# URC_ezFET_Lite.net
KiCad netlist of a schematic drawn in Altium Designer
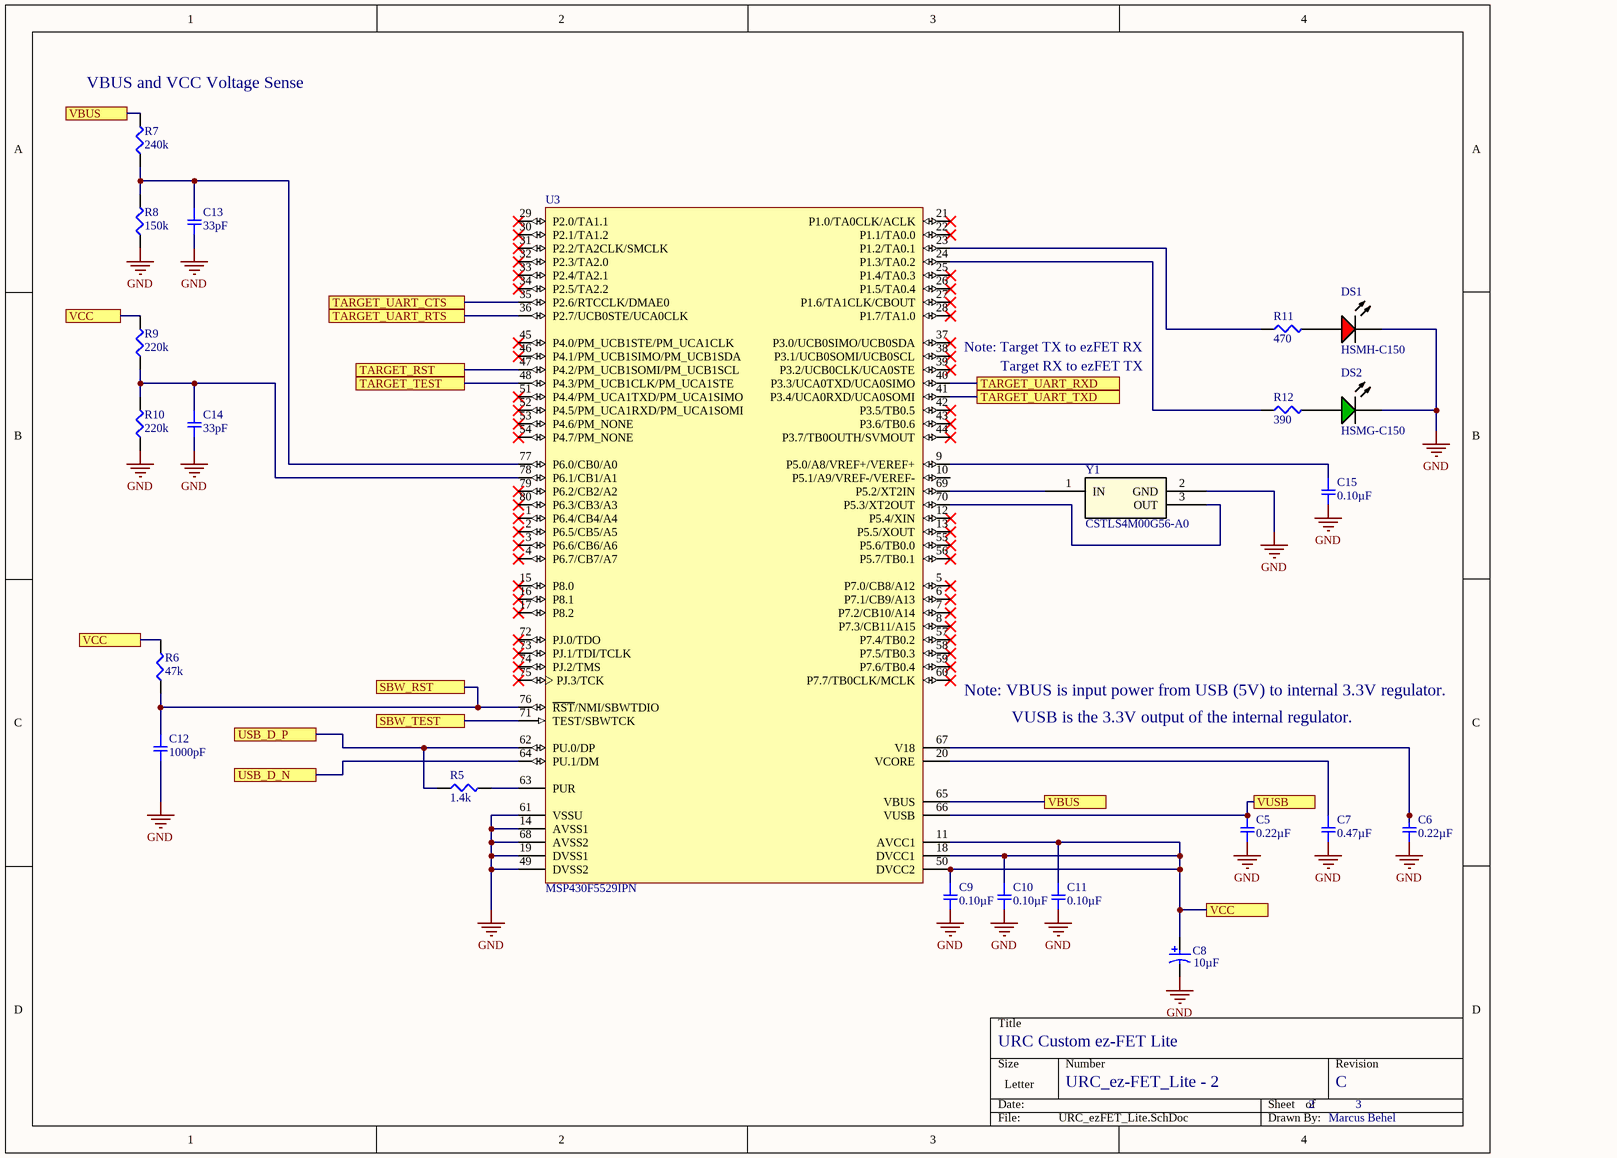
[diagram p0: URC_ezFET_Lite.SchDoc]

(export (version "E")
  (design (tool "Eeschema 10.0.6"))
  (components
    (comp (ref "C5")
      (value "0.22µF")
      (footprint "SMD-1206C")
      (description "CAP CER 0.22UF 50V X7R 1206")
      (fields
        (field (name "DIGI-KEY PART NUMBER") "490-8059-1-ND")
        (field (name "PART NUMBER") "GCM31MR71H224KA37L")
      )
      (libsource (lib "capacitor_murata_1206$") (part "GCM31MR71H224KA37L"))
    )
    (comp (ref "C6")
      (value "0.22µF")
      (footprint "SMD-1206C")
      (description "CAP CER 0.22UF 50V X7R 1206")
      (fields
        (field (name "DIGI-KEY PART NUMBER") "490-8059-1-ND")
        (field (name "PART NUMBER") "GCM31MR71H224KA37L")
      )
      (libsource (lib "capacitor_murata_1206$") (part "GCM31MR71H224KA37L"))
    )
    (comp (ref "C7")
      (value "0.47µF")
      (footprint "SMD-1206C")
      (description "CAP CER 0.47UF 50V X7R 1206")
      (fields
        (field (name "DIGI-KEY PART NUMBER") "490-8061-1-ND")
        (field (name "PART NUMBER") "GCM31MR71H474KA37L")
      )
      (libsource (lib "capacitor_murata_1206$") (part "GCM31MR71H474KA37L"))
    )
    (comp (ref "C8")
      (value "T491A106K010AT")
      (footprint "KEMT-A-3216-18-2_M")
      (description "Capacitor, Tantalum, 10 uF, +/- 10%, 10 V, -55 to 125 degC, 2-Pin SMD (1206), RoHS, Tape and Reel")
      (fields
        (field (name "TOLERANCE") "±10%")
        (field (name "MANUFACTURER") "Kemet")
        (field (name "CAPACITANCE") "10µF")
      )
      (libsource (lib "Altium Content Vault") (part "CAP-P-2"))
    )
    (comp (ref "C9")
      (value "0.10µF")
      (footprint "SMD-1206C")
      (description "CAP CER 0.1UF 50V X7R 1206")
      (fields
        (field (name "DIGI-KEY PART NUMBER") "490-11166-1-ND")
        (field (name "PART NUMBER") "GCM319R71H104KA37D")
      )
      (libsource (lib "capacitor_murata_1206$") (part "GCM319R71H104KA37D"))
    )
    (comp (ref "C10")
      (value "0.10µF")
      (footprint "SMD-1206C")
      (description "CAP CER 0.1UF 50V X7R 1206")
      (fields
        (field (name "DIGI-KEY PART NUMBER") "490-11166-1-ND")
        (field (name "PART NUMBER") "GCM319R71H104KA37D")
      )
      (libsource (lib "capacitor_murata_1206$") (part "GCM319R71H104KA37D"))
    )
    (comp (ref "C11")
      (value "0.10µF")
      (footprint "SMD-1206C")
      (description "CAP CER 0.1UF 50V X7R 1206")
      (fields
        (field (name "DIGI-KEY PART NUMBER") "490-11166-1-ND")
        (field (name "PART NUMBER") "GCM319R71H104KA37D")
      )
      (libsource (lib "capacitor_murata_1206$") (part "GCM319R71H104KA37D"))
    )
    (comp (ref "C12")
      (value "1000pF")
      (footprint "SMD-1206C")
      (description "CAP CER 1000PF 50V X7R 1206")
      (fields
        (field (name "DIGI-KEY PART NUMBER") "490-11610-1-ND")
        (field (name "PART NUMBER") "GRM319R71H102KA01D")
      )
      (libsource (lib "capacitor_murata_1206$") (part "GRM319R71H102KA01D"))
    )
    (comp (ref "C13")
      (value "33pF")
      (footprint "SMD-1206C")
      (description "CAP CER 33PF 630V U2J 1206")
      (fields
        (field (name "DIGI-KEY PART NUMBER") "490-5040-1-ND")
        (field (name "PART NUMBER") "GCM31A7U2J330JX01D")
      )
      (libsource (lib "capacitor_murata_1206$") (part "GCM31A7U2J330JX01D"))
    )
    (comp (ref "C14")
      (value "33pF")
      (footprint "SMD-1206C")
      (description "CAP CER 33PF 630V U2J 1206")
      (fields
        (field (name "DIGI-KEY PART NUMBER") "490-5040-1-ND")
        (field (name "PART NUMBER") "GCM31A7U2J330JX01D")
      )
      (libsource (lib "capacitor_murata_1206$") (part "GCM31A7U2J330JX01D"))
    )
    (comp (ref "C15")
      (value "0.10µF")
      (footprint "SMD-1206C")
      (description "CAP CER 0.1UF 250V X7R 1206")
      (fields
        (field (name "DIGI-KEY PART NUMBER") "490-12647-1-ND")
        (field (name "PART NUMBER") "GCJ31CR72E104KXJ3L")
      )
      (libsource (lib "capacitor_murata_1206$") (part "GCJ31CR72E104KXJ3L"))
    )
    (comp (ref "DS1")
      (value "HSMH-C150")
      (footprint "AVAG-HSMX-C150_V")
      (description "LED Uni-Color Red, 65 mW, 25 mA, -40 to 85 degC, 2-Pin SMD, RoHS, Tape and Reel")
      (fields (field (name "MANUFACTURER") "Avago"))
      (libsource (lib "Altium Content Vault") (part "LED-RED-AK-2"))
    )
    (comp (ref "DS2")
      (value "HSMG-C150")
      (footprint "AVAG-HSMX-C150_V")
      (description "Chip LED, Green, 65 mW, 25 mA, -40 to 85 degC, 2-Pin SMD, RoHS, Tape and Reel")
      (fields (field (name "MANUFACTURER") "Avago"))
      (libsource (lib "Altium Content Vault") (part "LED_GREEN_A1K2-2"))
    )
    (comp (ref "R5")
      (value "1.4k")
      (footprint "SMD-0805-RES")
      (description "RES SMD 1.4K OHM 1% 1/8W 0805")
      (fields
        (field (name "PART NUMBER") "ERJ-6ENF1401V")
        (field (name "DIGI-KEY PART NUMBER") "P1.40KCCT-ND")
      )
      (libsource (lib "Panasonic_ERJ_0805") (part "ERJ-6ENF1401V"))
    )
    (comp (ref "R6")
      (value "47k")
      (footprint "SMD-1206-RES")
      (description "RES SMD 47K OHM 5% 2/3W 1206")
      (fields (field (name "PART NUMBER") "ERJ-P08J473V") (field (name "DIGI-KEY PART NUMBER") "P47KALCT-ND"))
      (libsource (lib "Panasonic_ERJ_1206") (part "ERJ-P08J473V"))
    )
    (comp (ref "R7")
      (value "240k")
      (footprint "SMD-1206-RES")
      (description "RES SMD 240K OHM 5% 2/3W 1206")
      (fields
        (field (name "PART NUMBER") "ERJ-P08J244V")
        (field (name "DIGI-KEY PART NUMBER") "P240KALCT-ND")
      )
      (libsource (lib "Panasonic_ERJ_1206") (part "ERJ-P08J244V"))
    )
    (comp (ref "R8")
      (value "150k")
      (footprint "SMD-1206-RES")
      (description "RES SMD 150K OHM 5% 2/3W 1206")
      (fields
        (field (name "PART NUMBER") "ERJ-P08J154V")
        (field (name "DIGI-KEY PART NUMBER") "P150KALCT-ND")
      )
      (libsource (lib "Panasonic_ERJ_1206") (part "ERJ-P08J154V"))
    )
    (comp (ref "R9")
      (value "220k")
      (footprint "SMD-1206-RES")
      (description "RES SMD 220K OHM 5% 2/3W 1206")
      (fields
        (field (name "PART NUMBER") "ERJ-P08J224V")
        (field (name "DIGI-KEY PART NUMBER") "P220KALCT-ND")
      )
      (libsource (lib "Panasonic_ERJ_1206") (part "ERJ-P08J224V"))
    )
    (comp (ref "R10")
      (value "220k")
      (footprint "SMD-1206-RES")
      (description "RES SMD 220K OHM 5% 2/3W 1206")
      (fields
        (field (name "PART NUMBER") "ERJ-P08J224V")
        (field (name "DIGI-KEY PART NUMBER") "P220KALCT-ND")
      )
      (libsource (lib "Panasonic_ERJ_1206") (part "ERJ-P08J224V"))
    )
    (comp (ref "R11")
      (value "470")
      (footprint "SMD-1206-RES")
      (description "RES SMD 470 OHM 1% 1/4W 1206")
      (fields (field (name "PART NUMBER") "ERJ-8ENF4700V") (field (name "DIGI-KEY PART NUMBER") "P470FCT-ND"))
      (libsource (lib "Panasonic_ERJ_1206") (part "ERJ-8ENF4700V"))
    )
    (comp (ref "R12")
      (value "390")
      (footprint "SMD-1206-RES")
      (description "RES SMD 390 OHM 1% 1/4W 1206")
      (fields (field (name "PART NUMBER") "ERJ-8ENF3900V") (field (name "DIGI-KEY PART NUMBER") "P390FCT-ND"))
      (libsource (lib "Panasonic_ERJ_1206") (part "ERJ-8ENF3900V"))
    )
    (comp (ref "U3")
      (value "MSP430F5529IPN")
      (footprint "PN0080A_L")
      (fields (field (name "MANUFACTURER") "Texas Instruments"))
      (libsource (lib "Altium Content Vault") (part "TI-MSP430F552X_A-PN80"))
    )
    (comp (ref "Y1")
      (value "CSTLS4M00G56-A0")
      (footprint "CSTLS_G")
      (description "No Description Available")
      (fields (field (name "COPYRIGHT") "Copyright (C) 2018 Accelerated Designs. All rights reserved"))
      (libsource (lib "resonator") (part "CSTLS4M00G56-A0"))
    )
  )
  (nets
    (net (code "1") (name "/SBW_RST") (class "Default")
      (node (ref "C12") (pin "1") (pinfunction "1_1") (pintype "passive"))
      (node (ref "R6") (pin "1") (pinfunction "1_1") (pintype "passive"))
      (node (ref "U3") (pin "76") (pinfunction "~{RST}/NMI/SBWTDIO_76") (pintype "bidirectional"))
    )
    (net (code "2") (name "/SBW_TEST") (class "Default")
      (node (ref "U3") (pin "71") (pinfunction "TEST/SBWTCK_71") (pintype "input"))
    )
    (net (code "3") (name "/TARGET_RST") (class "Default")
      (node (ref "U3") (pin "47") (pinfunction "P4.2/PM_UCB1SOMI/PM_UCB1SCL_47") (pintype "bidirectional"))
    )
    (net (code "4") (name "/TARGET_TEST") (class "Default")
      (node (ref "U3") (pin "48") (pinfunction "P4.3/PM_UCB1CLK/PM_UCA1STE_48") (pintype "bidirectional"))
    )
    (net (code "5") (name "/TARGET_UART_CTS") (class "Default")
      (node (ref "U3") (pin "35") (pinfunction "P2.6/RTCCLK/DMAE0_35") (pintype "bidirectional"))
    )
    (net (code "6") (name "/TARGET_UART_RTS") (class "Default")
      (node (ref "U3") (pin "36") (pinfunction "P2.7/UCB0STE/UCA0CLK_36") (pintype "bidirectional"))
    )
    (net (code "7") (name "/TARGET_UART_RXD") (class "Default")
      (node (ref "U3") (pin "40") (pinfunction "P3.3/UCA0TXD/UCA0SIMO_40") (pintype "bidirectional"))
    )
    (net (code "8") (name "/TARGET_UART_TXD") (class "Default")
      (node (ref "U3") (pin "41") (pinfunction "P3.4/UCA0RXD/UCA0SOMI_41") (pintype "bidirectional"))
    )
    (net (code "9") (name "/USB_D_N") (class "Default")
      (node (ref "U3") (pin "64") (pinfunction "PU.1/DM_64") (pintype "bidirectional"))
    )
    (net (code "10") (name "/USB_D_P") (class "Default")
      (node (ref "R5") (pin "1") (pinfunction "1_1") (pintype "passive"))
      (node (ref "U3") (pin "62") (pinfunction "PU.0/DP_62") (pintype "bidirectional"))
    )
    (net (code "11") (name "/VBUS") (class "Default")
      (node (ref "R7") (pin "2") (pinfunction "2_2") (pintype "passive"))
      (node (ref "U3") (pin "65") (pinfunction "VBUS_65") (pintype "power_in"))
    )
    (net (code "12") (name "/VCC") (class "Default")
      (node (ref "C10") (pin "1") (pinfunction "1_1") (pintype "passive"))
      (node (ref "C11") (pin "1") (pinfunction "1_1") (pintype "passive"))
      (node (ref "C8") (pin "1") (pinfunction "1_1") (pintype "passive"))
      (node (ref "C9") (pin "1") (pinfunction "1_1") (pintype "passive"))
      (node (ref "R6") (pin "2") (pinfunction "2_2") (pintype "passive"))
      (node (ref "R9") (pin "2") (pinfunction "2_2") (pintype "passive"))
      (node (ref "U3") (pin "11") (pinfunction "AVCC1_11") (pintype "power_in"))
      (node (ref "U3") (pin "18") (pinfunction "DVCC1_18") (pintype "power_in"))
      (node (ref "U3") (pin "50") (pinfunction "DVCC2_50") (pintype "power_in"))
    )
    (net (code "13") (name "/VUSB") (class "Default")
      (node (ref "C5") (pin "1") (pinfunction "1_1") (pintype "passive"))
      (node (ref "U3") (pin "66") (pinfunction "VUSB_66") (pintype "power_in"))
    )
    (net (code "14") (name "GND") (class "Default")
      (node (ref "C10") (pin "2") (pinfunction "2_2") (pintype "passive"))
      (node (ref "C11") (pin "2") (pinfunction "2_2") (pintype "passive"))
      (node (ref "C12") (pin "2") (pinfunction "2_2") (pintype "passive"))
      (node (ref "C13") (pin "2") (pinfunction "2_2") (pintype "passive"))
      (node (ref "C14") (pin "2") (pinfunction "2_2") (pintype "passive"))
      (node (ref "C15") (pin "2") (pinfunction "2_2") (pintype "passive"))
      (node (ref "C5") (pin "2") (pinfunction "2_2") (pintype "passive"))
      (node (ref "C6") (pin "2") (pinfunction "2_2") (pintype "passive"))
      (node (ref "C7") (pin "2") (pinfunction "2_2") (pintype "passive"))
      (node (ref "C8") (pin "2") (pinfunction "2_2") (pintype "passive"))
      (node (ref "C9") (pin "2") (pinfunction "2_2") (pintype "passive"))
      (node (ref "DS1") (pin "2") (pinfunction "K_2") (pintype "passive"))
      (node (ref "DS2") (pin "2") (pinfunction "K_2") (pintype "passive"))
      (node (ref "R10") (pin "1") (pinfunction "1_1") (pintype "passive"))
      (node (ref "R8") (pin "1") (pinfunction "1_1") (pintype "passive"))
      (node (ref "U3") (pin "14") (pinfunction "AVSS1_14") (pintype "power_in"))
      (node (ref "U3") (pin "19") (pinfunction "DVSS1_19") (pintype "power_in"))
      (node (ref "U3") (pin "49") (pinfunction "DVSS2_49") (pintype "power_in"))
      (node (ref "U3") (pin "61") (pinfunction "VSSU_61") (pintype "power_in"))
      (node (ref "U3") (pin "68") (pinfunction "AVSS2_68") (pintype "power_in"))
      (node (ref "Y1") (pin "2") (pinfunction "GND_2") (pintype "passive"))
    )
    (net (code "15") (name "Net-(DS1-A)") (class "Default")
      (node (ref "DS1") (pin "1") (pinfunction "A_1") (pintype "passive"))
      (node (ref "R11") (pin "2") (pinfunction "2_2") (pintype "passive"))
    )
    (net (code "16") (name "Net-(DS2-A)") (class "Default")
      (node (ref "DS2") (pin "1") (pinfunction "A_1") (pintype "passive"))
      (node (ref "R12") (pin "2") (pinfunction "2_2") (pintype "passive"))
    )
    (net (code "17") (name "Net-(U3-P1.2{slash}TA0.1)") (class "Default")
      (node (ref "R11") (pin "1") (pinfunction "1_1") (pintype "passive"))
      (node (ref "U3") (pin "23") (pinfunction "P1.2/TA0.1_23") (pintype "bidirectional"))
    )
    (net (code "18") (name "Net-(U3-P1.3{slash}TA0.2)") (class "Default")
      (node (ref "R12") (pin "1") (pinfunction "1_1") (pintype "passive"))
      (node (ref "U3") (pin "24") (pinfunction "P1.3/TA0.2_24") (pintype "bidirectional"))
    )
    (net (code "19") (name "Net-(U3-P5.0{slash}A8{slash}VREF+{slash}VEREF+)") (class "Default")
      (node (ref "C15") (pin "1") (pinfunction "1_1") (pintype "passive"))
      (node (ref "U3") (pin "9") (pinfunction "P5.0/A8/VREF+/VEREF+_9") (pintype "bidirectional"))
    )
    (net (code "20") (name "Net-(U3-P5.2{slash}XT2IN)") (class "Default")
      (node (ref "U3") (pin "69") (pinfunction "P5.2/XT2IN_69") (pintype "bidirectional"))
      (node (ref "Y1") (pin "1") (pinfunction "IN_1") (pintype "passive"))
    )
    (net (code "21") (name "Net-(U3-P5.3{slash}XT2OUT)") (class "Default")
      (node (ref "U3") (pin "70") (pinfunction "P5.3/XT2OUT_70") (pintype "bidirectional"))
      (node (ref "Y1") (pin "3") (pinfunction "OUT_3") (pintype "passive"))
    )
    (net (code "22") (name "Net-(U3-P6.0{slash}CB0{slash}A0)") (class "Default")
      (node (ref "C13") (pin "1") (pinfunction "1_1") (pintype "passive"))
      (node (ref "R7") (pin "1") (pinfunction "1_1") (pintype "passive"))
      (node (ref "R8") (pin "2") (pinfunction "2_2") (pintype "passive"))
      (node (ref "U3") (pin "77") (pinfunction "P6.0/CB0/A0_77") (pintype "bidirectional"))
    )
    (net (code "23") (name "Net-(U3-P6.1{slash}CB1{slash}A1)") (class "Default")
      (node (ref "C14") (pin "1") (pinfunction "1_1") (pintype "passive"))
      (node (ref "R10") (pin "2") (pinfunction "2_2") (pintype "passive"))
      (node (ref "R9") (pin "1") (pinfunction "1_1") (pintype "passive"))
      (node (ref "U3") (pin "78") (pinfunction "P6.1/CB1/A1_78") (pintype "bidirectional"))
    )
    (net (code "24") (name "Net-(U3-PUR)") (class "Default")
      (node (ref "R5") (pin "2") (pinfunction "2_2") (pintype "passive"))
      (node (ref "U3") (pin "63") (pinfunction "PUR_63") (pintype "passive"))
    )
    (net (code "25") (name "Net-(U3-V18)") (class "Default")
      (node (ref "C6") (pin "1") (pinfunction "1_1") (pintype "passive"))
      (node (ref "U3") (pin "67") (pinfunction "V18_67") (pintype "passive"))
    )
    (net (code "26") (name "Net-(U3-VCORE)") (class "Default")
      (node (ref "C7") (pin "1") (pinfunction "1_1") (pintype "passive"))
      (node (ref "U3") (pin "20") (pinfunction "VCORE_20") (pintype "passive"))
    )
    (net (code "27") (name "unconnected-(U3-P1.0{slash}TA0CLK{slash}ACLK-Pad21)") (class "Default")
      (node (ref "U3") (pin "21") (pinfunction "P1.0/TA0CLK/ACLK_21") (pintype "bidirectional+no_connect"))
    )
    (net (code "28") (name "unconnected-(U3-P1.1{slash}TA0.0-Pad22)") (class "Default")
      (node (ref "U3") (pin "22") (pinfunction "P1.1/TA0.0_22") (pintype "bidirectional+no_connect"))
    )
    (net (code "29") (name "unconnected-(U3-P1.4{slash}TA0.3-Pad25)") (class "Default")
      (node (ref "U3") (pin "25") (pinfunction "P1.4/TA0.3_25") (pintype "bidirectional+no_connect"))
    )
    (net (code "30") (name "unconnected-(U3-P1.5{slash}TA0.4-Pad26)") (class "Default")
      (node (ref "U3") (pin "26") (pinfunction "P1.5/TA0.4_26") (pintype "bidirectional+no_connect"))
    )
    (net (code "31") (name "unconnected-(U3-P1.6{slash}TA1CLK{slash}CBOUT-Pad27)") (class "Default")
      (node (ref "U3") (pin "27") (pinfunction "P1.6/TA1CLK/CBOUT_27") (pintype "bidirectional+no_connect"))
    )
    (net (code "32") (name "unconnected-(U3-P1.7{slash}TA1.0-Pad28)") (class "Default")
      (node (ref "U3") (pin "28") (pinfunction "P1.7/TA1.0_28") (pintype "bidirectional+no_connect"))
    )
    (net (code "33") (name "unconnected-(U3-P2.0{slash}TA1.1-Pad29)") (class "Default")
      (node (ref "U3") (pin "29") (pinfunction "P2.0/TA1.1_29") (pintype "bidirectional+no_connect"))
    )
    (net (code "34") (name "unconnected-(U3-P2.1{slash}TA1.2-Pad30)") (class "Default")
      (node (ref "U3") (pin "30") (pinfunction "P2.1/TA1.2_30") (pintype "bidirectional+no_connect"))
    )
    (net (code "35") (name "unconnected-(U3-P2.2{slash}TA2CLK{slash}SMCLK-Pad31)") (class "Default")
      (node (ref "U3") (pin "31") (pinfunction "P2.2/TA2CLK/SMCLK_31") (pintype "bidirectional+no_connect"))
    )
    (net (code "36") (name "unconnected-(U3-P2.3{slash}TA2.0-Pad32)") (class "Default")
      (node (ref "U3") (pin "32") (pinfunction "P2.3/TA2.0_32") (pintype "bidirectional+no_connect"))
    )
    (net (code "37") (name "unconnected-(U3-P2.4{slash}TA2.1-Pad33)") (class "Default")
      (node (ref "U3") (pin "33") (pinfunction "P2.4/TA2.1_33") (pintype "bidirectional+no_connect"))
    )
    (net (code "38") (name "unconnected-(U3-P2.5{slash}TA2.2-Pad34)") (class "Default")
      (node (ref "U3") (pin "34") (pinfunction "P2.5/TA2.2_34") (pintype "bidirectional+no_connect"))
    )
    (net (code "39") (name "unconnected-(U3-P3.0{slash}UCB0SIMO{slash}UCB0SDA-Pad37)") (class "Default")
      (node (ref "U3") (pin "37") (pinfunction "P3.0/UCB0SIMO/UCB0SDA_37") (pintype "bidirectional+no_connect"))
    )
    (net (code "40") (name "unconnected-(U3-P3.1{slash}UCB0SOMI{slash}UCB0SCL-Pad38)") (class "Default")
      (node (ref "U3") (pin "38") (pinfunction "P3.1/UCB0SOMI/UCB0SCL_38") (pintype "bidirectional+no_connect"))
    )
    (net (code "41") (name "unconnected-(U3-P3.2{slash}UCB0CLK{slash}UCA0STE-Pad39)") (class "Default")
      (node (ref "U3") (pin "39") (pinfunction "P3.2/UCB0CLK/UCA0STE_39") (pintype "bidirectional+no_connect"))
    )
    (net (code "42") (name "unconnected-(U3-P3.5{slash}TB0.5-Pad42)") (class "Default")
      (node (ref "U3") (pin "42") (pinfunction "P3.5/TB0.5_42") (pintype "bidirectional+no_connect"))
    )
    (net (code "43") (name "unconnected-(U3-P3.6{slash}TB0.6-Pad43)") (class "Default")
      (node (ref "U3") (pin "43") (pinfunction "P3.6/TB0.6_43") (pintype "bidirectional+no_connect"))
    )
    (net (code "44") (name "unconnected-(U3-P3.7{slash}TB0OUTH{slash}SVMOUT-Pad44)") (class "Default")
      (node (ref "U3") (pin "44") (pinfunction "P3.7/TB0OUTH/SVMOUT_44") (pintype "bidirectional+no_connect"))
    )
    (net (code "45") (name "unconnected-(U3-P4.0{slash}PM_UCB1STE{slash}PM_UCA1CLK-Pad45)") (class "Default")
      (node (ref "U3") (pin "45") (pinfunction "P4.0/PM_UCB1STE/PM_UCA1CLK_45") (pintype "bidirectional+no_connect"))
    )
    (net (code "46") (name "unconnected-(U3-P4.1{slash}PM_UCB1SIMO{slash}PM_UCB1SDA-Pad46)") (class "Default")
      (node (ref "U3") (pin "46") (pinfunction "P4.1/PM_UCB1SIMO/PM_UCB1SDA_46") (pintype "bidirectional+no_connect"))
    )
    (net (code "47") (name "unconnected-(U3-P4.4{slash}PM_UCA1TXD{slash}PM_UCA1SIMO-Pad51)") (class "Default")
      (node (ref "U3") (pin "51") (pinfunction "P4.4/PM_UCA1TXD/PM_UCA1SIMO_51") (pintype "bidirectional+no_connect"))
    )
    (net (code "48") (name "unconnected-(U3-P4.5{slash}PM_UCA1RXD{slash}PM_UCA1SOMI-Pad52)") (class "Default")
      (node (ref "U3") (pin "52") (pinfunction "P4.5/PM_UCA1RXD/PM_UCA1SOMI_52") (pintype "bidirectional+no_connect"))
    )
    (net (code "49") (name "unconnected-(U3-P4.6{slash}PM_NONE-Pad53)") (class "Default")
      (node (ref "U3") (pin "53") (pinfunction "P4.6/PM_NONE_53") (pintype "bidirectional+no_connect"))
    )
    (net (code "50") (name "unconnected-(U3-P4.7{slash}PM_NONE-Pad54)") (class "Default")
      (node (ref "U3") (pin "54") (pinfunction "P4.7/PM_NONE_54") (pintype "bidirectional+no_connect"))
    )
    (net (code "51") (name "unconnected-(U3-P5.1{slash}A9{slash}VREF-{slash}VEREF--Pad10)") (class "Default")
      (node (ref "U3") (pin "10") (pinfunction "P5.1/A9/VREF-/VEREF-_10") (pintype "bidirectional"))
    )
    (net (code "52") (name "unconnected-(U3-P5.4{slash}XIN-Pad12)") (class "Default")
      (node (ref "U3") (pin "12") (pinfunction "P5.4/XIN_12") (pintype "bidirectional+no_connect"))
    )
    (net (code "53") (name "unconnected-(U3-P5.5{slash}XOUT-Pad13)") (class "Default")
      (node (ref "U3") (pin "13") (pinfunction "P5.5/XOUT_13") (pintype "bidirectional+no_connect"))
    )
    (net (code "54") (name "unconnected-(U3-P5.6{slash}TB0.0-Pad55)") (class "Default")
      (node (ref "U3") (pin "55") (pinfunction "P5.6/TB0.0_55") (pintype "bidirectional+no_connect"))
    )
    (net (code "55") (name "unconnected-(U3-P5.7{slash}TB0.1-Pad56)") (class "Default")
      (node (ref "U3") (pin "56") (pinfunction "P5.7/TB0.1_56") (pintype "bidirectional+no_connect"))
    )
    (net (code "56") (name "unconnected-(U3-P6.2{slash}CB2{slash}A2-Pad79)") (class "Default")
      (node (ref "U3") (pin "79") (pinfunction "P6.2/CB2/A2_79") (pintype "bidirectional+no_connect"))
    )
    (net (code "57") (name "unconnected-(U3-P6.3{slash}CB3{slash}A3-Pad80)") (class "Default")
      (node (ref "U3") (pin "80") (pinfunction "P6.3/CB3/A3_80") (pintype "bidirectional+no_connect"))
    )
    (net (code "58") (name "unconnected-(U3-P6.4{slash}CB4{slash}A4-Pad1)") (class "Default")
      (node (ref "U3") (pin "1") (pinfunction "P6.4/CB4/A4_1") (pintype "bidirectional+no_connect"))
    )
    (net (code "59") (name "unconnected-(U3-P6.5{slash}CB5{slash}A5-Pad2)") (class "Default")
      (node (ref "U3") (pin "2") (pinfunction "P6.5/CB5/A5_2") (pintype "bidirectional+no_connect"))
    )
    (net (code "60") (name "unconnected-(U3-P6.6{slash}CB6{slash}A6-Pad3)") (class "Default")
      (node (ref "U3") (pin "3") (pinfunction "P6.6/CB6/A6_3") (pintype "bidirectional+no_connect"))
    )
    (net (code "61") (name "unconnected-(U3-P6.7{slash}CB7{slash}A7-Pad4)") (class "Default")
      (node (ref "U3") (pin "4") (pinfunction "P6.7/CB7/A7_4") (pintype "bidirectional+no_connect"))
    )
    (net (code "62") (name "unconnected-(U3-P7.0{slash}CB8{slash}A12-Pad5)") (class "Default")
      (node (ref "U3") (pin "5") (pinfunction "P7.0/CB8/A12_5") (pintype "bidirectional+no_connect"))
    )
    (net (code "63") (name "unconnected-(U3-P7.1{slash}CB9{slash}A13-Pad6)") (class "Default")
      (node (ref "U3") (pin "6") (pinfunction "P7.1/CB9/A13_6") (pintype "bidirectional+no_connect"))
    )
    (net (code "64") (name "unconnected-(U3-P7.2{slash}CB10{slash}A14-Pad7)") (class "Default")
      (node (ref "U3") (pin "7") (pinfunction "P7.2/CB10/A14_7") (pintype "bidirectional+no_connect"))
    )
    (net (code "65") (name "unconnected-(U3-P7.3{slash}CB11{slash}A15-Pad8)") (class "Default")
      (node (ref "U3") (pin "8") (pinfunction "P7.3/CB11/A15_8") (pintype "bidirectional+no_connect"))
    )
    (net (code "66") (name "unconnected-(U3-P7.4{slash}TB0.2-Pad57)") (class "Default")
      (node (ref "U3") (pin "57") (pinfunction "P7.4/TB0.2_57") (pintype "bidirectional+no_connect"))
    )
    (net (code "67") (name "unconnected-(U3-P7.5{slash}TB0.3-Pad58)") (class "Default")
      (node (ref "U3") (pin "58") (pinfunction "P7.5/TB0.3_58") (pintype "bidirectional+no_connect"))
    )
    (net (code "68") (name "unconnected-(U3-P7.6{slash}TB0.4-Pad59)") (class "Default")
      (node (ref "U3") (pin "59") (pinfunction "P7.6/TB0.4_59") (pintype "bidirectional+no_connect"))
    )
    (net (code "69") (name "unconnected-(U3-P7.7{slash}TB0CLK{slash}MCLK-Pad60)") (class "Default")
      (node (ref "U3") (pin "60") (pinfunction "P7.7/TB0CLK/MCLK_60") (pintype "bidirectional+no_connect"))
    )
    (net (code "70") (name "unconnected-(U3-P8.0-Pad15)") (class "Default")
      (node (ref "U3") (pin "15") (pinfunction "P8.0_15") (pintype "bidirectional+no_connect"))
    )
    (net (code "71") (name "unconnected-(U3-P8.1-Pad16)") (class "Default")
      (node (ref "U3") (pin "16") (pinfunction "P8.1_16") (pintype "bidirectional+no_connect"))
    )
    (net (code "72") (name "unconnected-(U3-P8.2-Pad17)") (class "Default")
      (node (ref "U3") (pin "17") (pinfunction "P8.2_17") (pintype "bidirectional+no_connect"))
    )
    (net (code "73") (name "unconnected-(U3-PJ.0{slash}TDO-Pad72)") (class "Default")
      (node (ref "U3") (pin "72") (pinfunction "PJ.0/TDO_72") (pintype "bidirectional+no_connect"))
    )
    (net (code "74") (name "unconnected-(U3-PJ.1{slash}TDI{slash}TCLK-Pad73)") (class "Default")
      (node (ref "U3") (pin "73") (pinfunction "PJ.1/TDI/TCLK_73") (pintype "bidirectional+no_connect"))
    )
    (net (code "75") (name "unconnected-(U3-PJ.2{slash}TMS-Pad74)") (class "Default")
      (node (ref "U3") (pin "74") (pinfunction "PJ.2/TMS_74") (pintype "bidirectional+no_connect"))
    )
    (net (code "76") (name "unconnected-(U3-PJ.3{slash}TCK-Pad75)") (class "Default")
      (node (ref "U3") (pin "75") (pinfunction "PJ.3/TCK_75") (pintype "bidirectional+no_connect"))
    )
  )
)
